# AJAX_PR1.net
KiCad netlist of a schematic drawn in Altium Designer
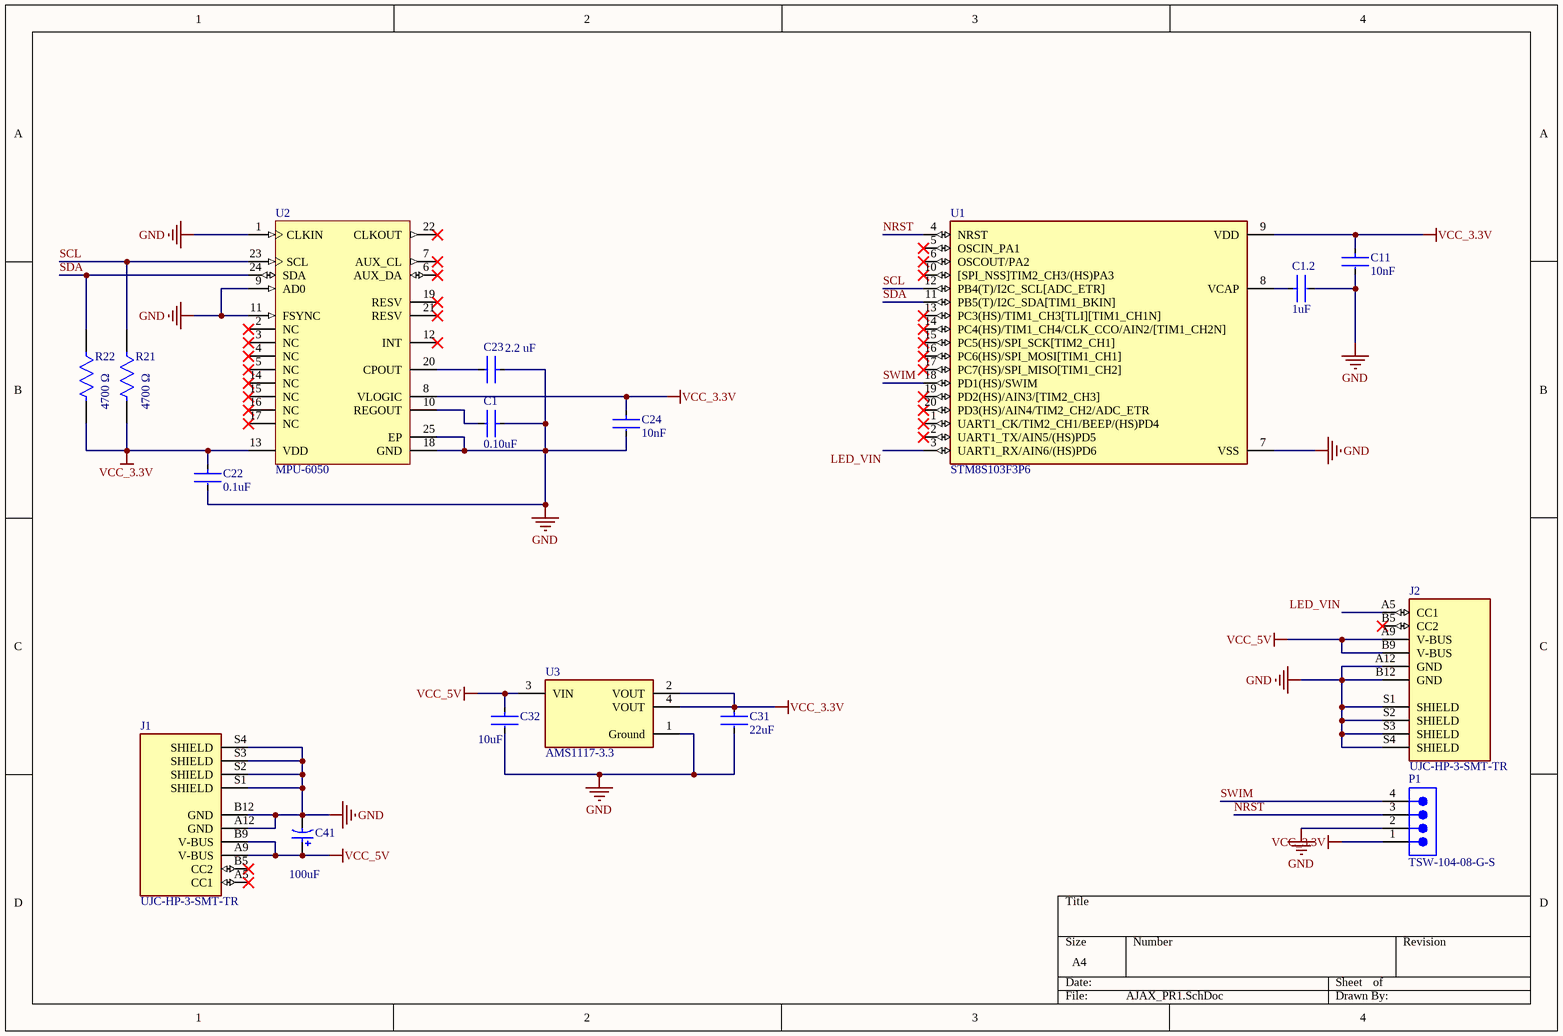
[diagram p0: AJAX_PR1.SchDoc]

(export (version "E")
  (design (tool "Eeschema 10.0.6"))
  (components
    (comp (ref "C1")
      (value "0.10uF")
      (footprint "FP-GRM033-0_03-IPC_A")
      (description "Chip Multilayer Ceramic Capacitors for General Purpose, 0201, 0.10uF, X6S, 22%, 10%, 4V")
      (fields (field (name "TOLERANCE") "10%"))
      (libsource (lib "Altium Content Vault") (part "b4654b650e69147ec39a6b967a45e02"))
    )
    (comp (ref "C1.2")
      (value "1uF")
      (footprint "FP-GCG31C-0_3-IPC_A")
      (libsource (lib "Altium Content Vault") (part "02cd4be3c70576c341d710602a673aa"))
    )
    (comp (ref "C11")
      (value "10nF")
      (footprint "FP-GRM155-0_05-IPC_C")
      (description "Chip Multilayer Ceramic Capacitors for General Purpose, 0402, 10000pF, X7R, 15%, 10%, 50V")
      (fields (field (name "TOLERANCE") "10%") (field (name "VOLTAGE") "25V"))
      (libsource (lib "Altium Content Vault") (part "02cd4be3c70576c341d710602a673aa"))
    )
    (comp (ref "C22")
      (value "0.1uF")
      (footprint "FP-GRM033-0_03-IPC_A")
      (description "Chip Multilayer Ceramic Capacitors for General Purpose, 0201, 0.10uF, X6S, 22%, 10%, 4V")
      (fields (field (name "TOLERANCE") "10%"))
      (libsource (lib "Altium Content Vault") (part "b4654b650e69147ec39a6b967a45e02"))
    )
    (comp (ref "C23")
      (value "2.2 uF")
      (footprint "FP-CGA6P-IPC_C")
      (description "Cap Ceramic 2.2uF 50V X7R 10% Pad SMD 1210 +125°C Automotive T/R")
      (fields (field (name "TOLERANCE") "10%"))
      (libsource (lib "Altium Content Vault") (part "b4654b650e69147ec39a6b967a45e02"))
    )
    (comp (ref "C24")
      (value "10nF")
      (footprint "FP-GRM155-0_05-IPC_C")
      (description "Chip Multilayer Ceramic Capacitors for General Purpose, 0402, 10000pF, X7R, 15%, 10%, 50V")
      (fields (field (name "TOLERANCE") "10%") (field (name "VOLTAGE") "25V"))
      (libsource (lib "Altium Content Vault") (part "02cd4be3c70576c341d710602a673aa"))
    )
    (comp (ref "C31")
      (value "22uF")
      (footprint "FP-GRM188-0_2-IPC_C")
      (description "Chip Multilayer Ceramic Capacitors for General Purpose, 0603, 22uF, X5R, 15%, 20%, 10V")
      (fields (field (name "TOLERANCE") "20%"))
      (libsource (lib "Altium Content Vault") (part "11868f565c42a9108669ba33697ecf6"))
    )
    (comp (ref "C32")
      (value "10uF")
      (footprint "FP-GRM188-0_1-e0_2_0_55-IPC_A")
      (description "Chip Multilayer Ceramic Capacitors for General Purpose, 0603, 10uF, X5R, 15%, 20%, 6.3V")
      (fields (field (name "VOLTAGE") "6.3V") (field (name "TOLERANCE") "20%"))
      (libsource (lib "Altium Content Vault") (part "02cd4be3c70576c341d710602a673aa"))
    )
    (comp (ref "C41")
      (value "100uF")
      (footprint "PNSC-FK-V-D8_V")
      (fields (field (name "MANUFACTURER") "Panasonic"))
      (libsource (lib "Altium Content Vault") (part "CAP-P-2"))
    )
    (comp (ref "J1")
      (value "UJC-HP-3-SMT-TR")
      (footprint "CUI_UJC-HP-3-SMT-TR")
      (libsource (lib "UJC-HP-3-SMT-TR") (part "UJC-HP-3-SMT-TR"))
    )
    (comp (ref "J2")
      (value "UJC-HP-3-SMT-TR")
      (footprint "CUI_UJC-HP-3-SMT-TR")
      (libsource (lib "") (part "UJC-HP-3-SMT-TR_1"))
    )
    (comp (ref "P1")
      (value "TSW-104-08-G-S")
      (footprint "SMTC-TSW-104-08-X-S")
      (description "0.025\" SQ Post Header, Through-hole, Vertical, -55 to 125 degC, 2.54 mm Pitch, 4-Pin, Male, RoHS")
      (fields (field (name "MANUFACTURER") "Samtec"))
      (libsource (lib "Altium Content Vault") (part "SMTC-TSW-104-08-X-S"))
    )
    (comp (ref "R21")
      (value "4700 Ω")
      (footprint "FP-RC1206-0_65-IPC_B")
      (description "RES SMD 4.7K OHM 1% 1/4W 1206")
      (fields (field (name "TOLERANCE") "1%"))
      (libsource (lib "Altium Content Vault") (part "1029c3af85768c4190bb7ad29bc67b5"))
    )
    (comp (ref "R22")
      (value "4700 Ω")
      (footprint "FP-RC1206-0_65-IPC_B")
      (description "RES SMD 4.7K OHM 1% 1/4W 1206")
      (fields (field (name "TOLERANCE") "1%"))
      (libsource (lib "Altium Content Vault") (part "1029c3af85768c4190bb7ad29bc67b5"))
    )
    (comp (ref "U1")
      (value "STM8S103F3P6")
      (footprint "SOP65P640X120-20N")
      (description "STM8 series Microcontroller IC 8-Bit 16MHz 8KB (8K x 8) FLASH 20-TSSOP")
      (fields (field (name "MF") "STMicroelectronics"))
      (libsource (lib "STM8S103F3P6") (part "STM8S103F3P6"))
    )
    (comp (ref "U2")
      (value "MPU-6050")
      (footprint "IS-QFN-24_V")
      (fields (field (name "MANUFACTURER") "InvenSense"))
      (libsource (lib "Altium Content Vault") (part "IS-MPU-6050-QFN-24"))
    )
    (comp (ref "U3")
      (value "AMS1117-3.3")
      (footprint "FP-AMS1117-IPC_C")
      (description "LDO Voltage Regulators 1A, 3.3V")
      (fields
        (field (name "OCTOPART") "https://octopart.com/ams1117-3.3-advanced+monolithic+systems-25899300")
        (field (name "MANUFACTURER") "Advanced Monolithic Systems")
      )
      (libsource (lib "Altium Content Vault") (part "8bdbb5f8e77002000e30dd2845d0354"))
    )
  )
  (nets
    (net (code "1") (name "/LED_VIN") (class "Default")
      (node (ref "J2") (pin "A5") (pinfunction "CC1_A5") (pintype "bidirectional"))
      (node (ref "U1") (pin "3") (pinfunction "UART1_RX/AIN6/(HS)PD6_3") (pintype "bidirectional"))
    )
    (net (code "2") (name "/NRST") (class "Default")
      (node (ref "P1") (pin "3") (pinfunction "3_3") (pintype "passive"))
      (node (ref "U1") (pin "4") (pinfunction "NRST_4") (pintype "bidirectional"))
    )
    (net (code "3") (name "/SCL") (class "Default")
      (node (ref "R21") (pin "1") (pinfunction "1_1") (pintype "passive"))
      (node (ref "U1") (pin "12") (pinfunction "PB4(T)/I2C_SCL[ADC_ETR]_12") (pintype "bidirectional"))
      (node (ref "U2") (pin "23") (pinfunction "SCL_23") (pintype "input"))
    )
    (net (code "4") (name "/SDA") (class "Default")
      (node (ref "R22") (pin "1") (pinfunction "1_1") (pintype "passive"))
      (node (ref "U1") (pin "11") (pinfunction "PB5(T)/I2C_SDA[TIM1_BKIN]_11") (pintype "bidirectional"))
      (node (ref "U2") (pin "24") (pinfunction "SDA_24") (pintype "bidirectional"))
    )
    (net (code "5") (name "/SWIM") (class "Default")
      (node (ref "P1") (pin "4") (pinfunction "4_4") (pintype "passive"))
      (node (ref "U1") (pin "18") (pinfunction "PD1(HS)/SWIM_18") (pintype "bidirectional"))
    )
    (net (code "6") (name "GND") (class "Default")
      (node (ref "C1") (pin "1") (pinfunction "1_1") (pintype "passive"))
      (node (ref "C1.2") (pin "2") (pinfunction "2_2") (pintype "passive"))
      (node (ref "C11") (pin "2") (pinfunction "2_2") (pintype "passive"))
      (node (ref "C22") (pin "2") (pinfunction "2_2") (pintype "passive"))
      (node (ref "C23") (pin "1") (pinfunction "1_1") (pintype "passive"))
      (node (ref "C24") (pin "2") (pinfunction "2_2") (pintype "passive"))
      (node (ref "C31") (pin "2") (pinfunction "2_2") (pintype "passive"))
      (node (ref "C32") (pin "2") (pinfunction "2_2") (pintype "passive"))
      (node (ref "C41") (pin "2") (pinfunction "2_2") (pintype "passive"))
      (node (ref "J1") (pin "A12") (pinfunction "GND_A12") (pintype "power_in"))
      (node (ref "J1") (pin "B12") (pinfunction "GND_B12") (pintype "power_in"))
      (node (ref "J1") (pin "S1") (pinfunction "SHIELD_S1") (pintype "passive"))
      (node (ref "J1") (pin "S2") (pinfunction "SHIELD_S2") (pintype "passive"))
      (node (ref "J1") (pin "S3") (pinfunction "SHIELD_S3") (pintype "passive"))
      (node (ref "J1") (pin "S4") (pinfunction "SHIELD_S4") (pintype "passive"))
      (node (ref "J2") (pin "A12") (pinfunction "GND_A12") (pintype "power_in"))
      (node (ref "J2") (pin "B12") (pinfunction "GND_B12") (pintype "power_in"))
      (node (ref "J2") (pin "S1") (pinfunction "SHIELD_S1") (pintype "passive"))
      (node (ref "J2") (pin "S2") (pinfunction "SHIELD_S2") (pintype "passive"))
      (node (ref "J2") (pin "S3") (pinfunction "SHIELD_S3") (pintype "passive"))
      (node (ref "J2") (pin "S4") (pinfunction "SHIELD_S4") (pintype "passive"))
      (node (ref "P1") (pin "2") (pinfunction "2_2") (pintype "passive"))
      (node (ref "U1") (pin "7") (pinfunction "VSS_7") (pintype "power_in"))
      (node (ref "U2") (pin "1") (pinfunction "CLKIN_1") (pintype "input"))
      (node (ref "U2") (pin "11") (pinfunction "FSYNC_11") (pintype "input"))
      (node (ref "U2") (pin "18") (pinfunction "GND_18") (pintype "power_in"))
      (node (ref "U2") (pin "25") (pinfunction "EP_25") (pintype "power_in"))
      (node (ref "U2") (pin "9") (pinfunction "AD0_9") (pintype "input"))
      (node (ref "U3") (pin "1") (pinfunction "Ground_1") (pintype "power_in"))
    )
    (net (code "7") (name "Net-(U1-VCAP)") (class "Default")
      (node (ref "C1.2") (pin "1") (pinfunction "1_1") (pintype "passive"))
      (node (ref "U1") (pin "8") (pinfunction "VCAP_8") (pintype "passive"))
    )
    (net (code "8") (name "Net-(U2-CPOUT)") (class "Default")
      (node (ref "C23") (pin "2") (pinfunction "2_2") (pintype "passive"))
      (node (ref "U2") (pin "20") (pinfunction "CPOUT_20") (pintype "passive"))
    )
    (net (code "9") (name "Net-(U2-REGOUT)") (class "Default")
      (node (ref "C1") (pin "2") (pinfunction "2_2") (pintype "passive"))
      (node (ref "U2") (pin "10") (pinfunction "REGOUT_10") (pintype "passive"))
    )
    (net (code "10") (name "VCC_3.3V") (class "Default")
      (node (ref "C11") (pin "1") (pinfunction "1_1") (pintype "passive"))
      (node (ref "C22") (pin "1") (pinfunction "1_1") (pintype "passive"))
      (node (ref "C24") (pin "1") (pinfunction "1_1") (pintype "passive"))
      (node (ref "C31") (pin "1") (pinfunction "1_1") (pintype "passive"))
      (node (ref "P1") (pin "1") (pinfunction "1_1") (pintype "passive"))
      (node (ref "R21") (pin "2") (pinfunction "2_2") (pintype "passive"))
      (node (ref "R22") (pin "2") (pinfunction "2_2") (pintype "passive"))
      (node (ref "U1") (pin "9") (pinfunction "VDD_9") (pintype "power_in"))
      (node (ref "U2") (pin "13") (pinfunction "VDD_13") (pintype "power_in"))
      (node (ref "U2") (pin "8") (pinfunction "VLOGIC_8") (pintype "power_in"))
      (node (ref "U3") (pin "2") (pinfunction "VOUT_2") (pintype "passive"))
      (node (ref "U3") (pin "4") (pinfunction "VOUT_4") (pintype "passive"))
    )
    (net (code "11") (name "VCC_5V") (class "Default")
      (node (ref "C32") (pin "1") (pinfunction "1_1") (pintype "passive"))
      (node (ref "C41") (pin "1") (pinfunction "1_1") (pintype "passive"))
      (node (ref "J1") (pin "A9") (pinfunction "V-BUS_A9") (pintype "power_in"))
      (node (ref "J1") (pin "B9") (pinfunction "V-BUS_B9") (pintype "power_in"))
      (node (ref "J2") (pin "A9") (pinfunction "V-BUS_A9") (pintype "power_in"))
      (node (ref "J2") (pin "B9") (pinfunction "V-BUS_B9") (pintype "power_in"))
      (node (ref "U3") (pin "3") (pinfunction "VIN_3") (pintype "power_in"))
    )
    (net (code "12") (name "unconnected-(J1-CC1-PadA5)") (class "Default")
      (node (ref "J1") (pin "A5") (pinfunction "CC1_A5") (pintype "bidirectional+no_connect"))
    )
    (net (code "13") (name "unconnected-(J1-CC2-PadB5)") (class "Default")
      (node (ref "J1") (pin "B5") (pinfunction "CC2_B5") (pintype "bidirectional+no_connect"))
    )
    (net (code "14") (name "unconnected-(J2-CC2-PadB5)") (class "Default")
      (node (ref "J2") (pin "B5") (pinfunction "CC2_B5") (pintype "bidirectional+no_connect"))
    )
    (net (code "15") (name "unconnected-(U1-OSCIN_PA1-Pad5)") (class "Default")
      (node (ref "U1") (pin "5") (pinfunction "OSCIN_PA1_5") (pintype "bidirectional+no_connect"))
    )
    (net (code "16") (name "unconnected-(U1-OSCOUT{slash}PA2-Pad6)") (class "Default")
      (node (ref "U1") (pin "6") (pinfunction "OSCOUT/PA2_6") (pintype "bidirectional+no_connect"))
    )
    (net (code "17") (name "unconnected-(U1-PC3(HS){slash}TIM1_CH3[TLI][TIM1_CH1N]-Pad13)") (class "Default")
      (node (ref "U1") (pin "13") (pinfunction "PC3(HS)/TIM1_CH3[TLI][TIM1_CH1N]_13") (pintype "bidirectional+no_connect"))
    )
    (net (code "18") (name "unconnected-(U1-PC4(HS){slash}TIM1_CH4{slash}CLK_CCO{slash}AIN2{slash}[TIM1_CH2N]-Pad14)") (class "Default")
      (node (ref "U1") (pin "14") (pinfunction "PC4(HS)/TIM1_CH4/CLK_CCO/AIN2/[TIM1_CH2N]_14") (pintype "bidirectional+no_connect"))
    )
    (net (code "19") (name "unconnected-(U1-PC5(HS){slash}SPI_SCK[TIM2_CH1]-Pad15)") (class "Default")
      (node (ref "U1") (pin "15") (pinfunction "PC5(HS)/SPI_SCK[TIM2_CH1]_15") (pintype "bidirectional+no_connect"))
    )
    (net (code "20") (name "unconnected-(U1-PC6(HS){slash}SPI_MOSI[TIM1_CH1]-Pad16)") (class "Default")
      (node (ref "U1") (pin "16") (pinfunction "PC6(HS)/SPI_MOSI[TIM1_CH1]_16") (pintype "bidirectional+no_connect"))
    )
    (net (code "21") (name "unconnected-(U1-PC7(HS){slash}SPI_MISO[TIM1_CH2]-Pad17)") (class "Default")
      (node (ref "U1") (pin "17") (pinfunction "PC7(HS)/SPI_MISO[TIM1_CH2]_17") (pintype "bidirectional+no_connect"))
    )
    (net (code "22") (name "unconnected-(U1-PD2(HS){slash}AIN3{slash}[TIM2_CH3]-Pad19)") (class "Default")
      (node (ref "U1") (pin "19") (pinfunction "PD2(HS)/AIN3/[TIM2_CH3]_19") (pintype "bidirectional+no_connect"))
    )
    (net (code "23") (name "unconnected-(U1-PD3(HS){slash}AIN4{slash}TIM2_CH2{slash}ADC_ETR-Pad20)") (class "Default")
      (node (ref "U1") (pin "20") (pinfunction "PD3(HS)/AIN4/TIM2_CH2/ADC_ETR_20") (pintype "bidirectional+no_connect"))
    )
    (net (code "24") (name "unconnected-(U1-UART1_CK{slash}TIM2_CH1{slash}BEEP{slash}(HS)PD4-Pad1)") (class "Default")
      (node (ref "U1") (pin "1") (pinfunction "UART1_CK/TIM2_CH1/BEEP/(HS)PD4_1") (pintype "bidirectional+no_connect"))
    )
    (net (code "25") (name "unconnected-(U1-UART1_TX{slash}AIN5{slash}(HS)PD5-Pad2)") (class "Default")
      (node (ref "U1") (pin "2") (pinfunction "UART1_TX/AIN5/(HS)PD5_2") (pintype "bidirectional+no_connect"))
    )
    (net (code "26") (name "unconnected-(U1-[SPI_NSS]TIM2_CH3{slash}(HS)PA3-Pad10)") (class "Default")
      (node (ref "U1") (pin "10") (pinfunction "[SPI_NSS]TIM2_CH3/(HS)PA3_10") (pintype "bidirectional+no_connect"))
    )
    (net (code "27") (name "unconnected-(U2-AUX_CL-Pad7)") (class "Default")
      (node (ref "U2") (pin "7") (pinfunction "AUX_CL_7") (pintype "output+no_connect"))
    )
    (net (code "28") (name "unconnected-(U2-AUX_DA-Pad6)") (class "Default")
      (node (ref "U2") (pin "6") (pinfunction "AUX_DA_6") (pintype "bidirectional+no_connect"))
    )
    (net (code "29") (name "unconnected-(U2-CLKOUT-Pad22)") (class "Default")
      (node (ref "U2") (pin "22") (pinfunction "CLKOUT_22") (pintype "output+no_connect"))
    )
    (net (code "30") (name "unconnected-(U2-INT-Pad12)") (class "Default")
      (node (ref "U2") (pin "12") (pinfunction "INT_12") (pintype "open_collector+no_connect"))
    )
    (net (code "31") (name "unconnected-(U2-NC-Pad2)") (class "Default")
      (node (ref "U2") (pin "2") (pinfunction "NC_2") (pintype "passive+no_connect"))
    )
    (net (code "32") (name "unconnected-(U2-NC-Pad3)") (class "Default")
      (node (ref "U2") (pin "3") (pinfunction "NC_3") (pintype "passive+no_connect"))
    )
    (net (code "33") (name "unconnected-(U2-NC-Pad4)") (class "Default")
      (node (ref "U2") (pin "4") (pinfunction "NC_4") (pintype "passive+no_connect"))
    )
    (net (code "34") (name "unconnected-(U2-NC-Pad5)") (class "Default")
      (node (ref "U2") (pin "5") (pinfunction "NC_5") (pintype "passive+no_connect"))
    )
    (net (code "35") (name "unconnected-(U2-NC-Pad14)") (class "Default")
      (node (ref "U2") (pin "14") (pinfunction "NC_14") (pintype "passive+no_connect"))
    )
    (net (code "36") (name "unconnected-(U2-NC-Pad15)") (class "Default")
      (node (ref "U2") (pin "15") (pinfunction "NC_15") (pintype "passive+no_connect"))
    )
    (net (code "37") (name "unconnected-(U2-NC-Pad16)") (class "Default")
      (node (ref "U2") (pin "16") (pinfunction "NC_16") (pintype "passive+no_connect"))
    )
    (net (code "38") (name "unconnected-(U2-NC-Pad17)") (class "Default")
      (node (ref "U2") (pin "17") (pinfunction "NC_17") (pintype "passive+no_connect"))
    )
    (net (code "39") (name "unconnected-(U2-RESV-Pad19)") (class "Default")
      (node (ref "U2") (pin "19") (pinfunction "RESV_19") (pintype "passive+no_connect"))
    )
    (net (code "40") (name "unconnected-(U2-RESV-Pad21)") (class "Default")
      (node (ref "U2") (pin "21") (pinfunction "RESV_21") (pintype "passive+no_connect"))
    )
  )
)
